# driver1.net
KiCad netlist of a schematic drawn in EAGLE
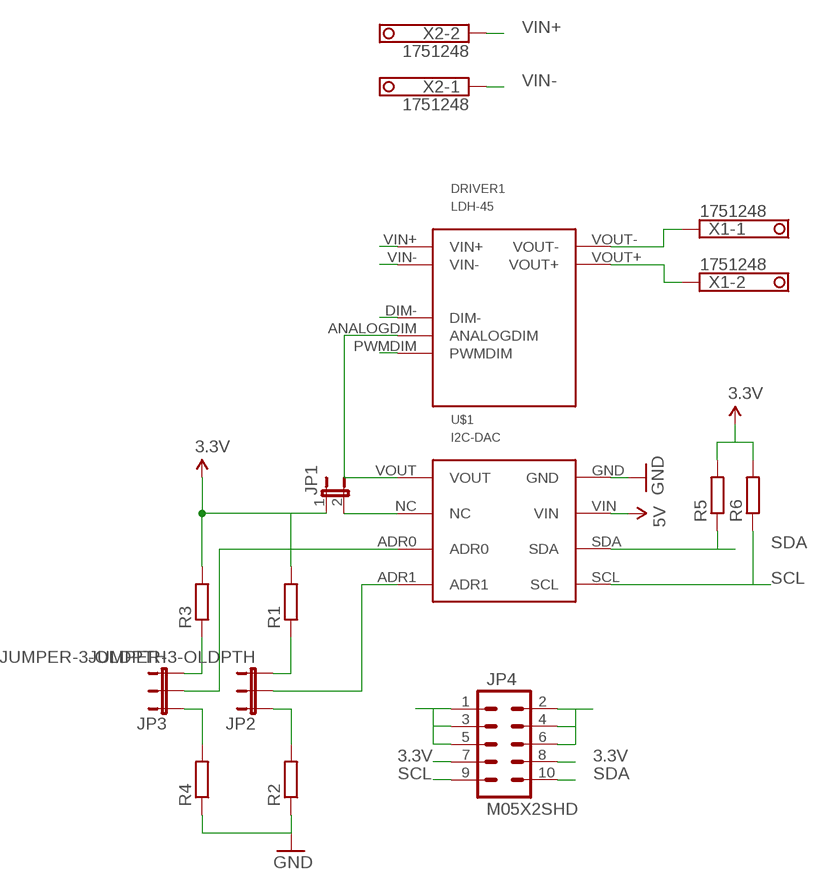
[diagram p0: schematic, sheet 1]

(export (version "E")
  (design (tool "Eeschema 10.0.6"))
  (components
    (comp (ref "DRIVER1")
      (value "LDH-45")
      (footprint "eagle-import:LDH-45")
      (libsource (lib "eagle-import") (part "LDH-45"))
    )
    (comp (ref "JP1")
      (value "JUMPER-2PTH_LOCK")
      (footprint "eagle-import:1X02_LOCK")
      (libsource (lib "eagle-import") (part "JUMPER-2PTH_LOCK"))
    )
    (comp (ref "JP2")
      (value "JUMPER-3-OLDPTH")
      (footprint "eagle-import:1X03")
      (libsource (lib "eagle-import") (part "JUMPER-3-OLDPTH"))
    )
    (comp (ref "JP3")
      (value "JUMPER-3-OLDPTH")
      (footprint "eagle-import:1X03")
      (libsource (lib "eagle-import") (part "JUMPER-3-OLDPTH"))
    )
    (comp (ref "JP4")
      (value "M05X2SHD")
      (footprint "eagle-import:2X5-SHROUDED")
      (libsource (lib "eagle-import") (part "M05X2SHD"))
    )
    (comp (ref "R1")
      (value "R-EU_R0603")
      (footprint "eagle-import:R0603")
      (libsource (lib "eagle-import") (part "R-EU_R0603"))
    )
    (comp (ref "R2")
      (value "R-EU_R0603")
      (footprint "eagle-import:R0603")
      (libsource (lib "eagle-import") (part "R-EU_R0603"))
    )
    (comp (ref "R3")
      (value "R-EU_R0603")
      (footprint "eagle-import:R0603")
      (libsource (lib "eagle-import") (part "R-EU_R0603"))
    )
    (comp (ref "R4")
      (value "R-EU_R0603")
      (footprint "eagle-import:R0603")
      (libsource (lib "eagle-import") (part "R-EU_R0603"))
    )
    (comp (ref "R5")
      (value "R-EU_R0603")
      (footprint "eagle-import:R0603")
      (libsource (lib "eagle-import") (part "R-EU_R0603"))
    )
    (comp (ref "R6")
      (value "R-EU_R0603")
      (footprint "eagle-import:R0603")
      (libsource (lib "eagle-import") (part "R-EU_R0603"))
    )
    (comp (ref "U$1")
      (value "I2C-DAC")
      (footprint "eagle-import:I2C-DAC")
      (libsource (lib "eagle-import") (part "I2C-DAC"))
    )
    (comp (ref "X1")
      (value "1751248")
      (footprint "eagle-import:1751248")
      (libsource (lib "eagle-import") (part "1751248"))
    )
    (comp (ref "X2")
      (value "1751248")
      (footprint "eagle-import:1751248")
      (fields (field (name "OC_FARNELL") "unknown") (field (name "OC_NEWARK") "unknown"))
      (libsource (lib "eagle-import") (part "1751248"))
    )
  )
  (nets
    (net (code "1") (name "/SCL") (class "Default")
      (node (ref "JP4") (pin "9") (pinfunction "9_9") (pintype "passive"))
      (node (ref "R6") (pin "1") (pinfunction "1_1") (pintype "passive"))
      (node (ref "U$1") (pin "SCL") (pinfunction "SCL_SCL") (pintype "bidirectional"))
    )
    (net (code "2") (name "/SDA") (class "Default")
      (node (ref "JP4") (pin "10") (pinfunction "10_10") (pintype "passive"))
      (node (ref "R5") (pin "1") (pinfunction "1_1") (pintype "passive"))
      (node (ref "U$1") (pin "SDA") (pinfunction "SDA_SDA") (pintype "bidirectional"))
    )
    (net (code "3") (name "/VIN+") (class "Default")
      (node (ref "DRIVER1") (pin "VIN+") (pinfunction "VIN+_VIN+") (pintype "bidirectional"))
      (node (ref "X2") (pin "2") (pinfunction "K_2") (pintype "passive"))
    )
    (net (code "4") (name "/VIN-") (class "Default")
      (node (ref "DRIVER1") (pin "VIN-") (pinfunction "VIN-_VIN-") (pintype "bidirectional"))
      (node (ref "X2") (pin "1") (pinfunction "K_1") (pintype "passive"))
    )
    (net (code "5") (name "3.3V") (class "Default")
      (node (ref "JP1") (pin "1") (pinfunction "1_1") (pintype "passive"))
      (node (ref "JP4") (pin "7") (pinfunction "7_7") (pintype "passive"))
      (node (ref "JP4") (pin "8") (pinfunction "8_8") (pintype "passive"))
      (node (ref "R1") (pin "2") (pinfunction "2_2") (pintype "passive"))
      (node (ref "R3") (pin "2") (pinfunction "2_2") (pintype "passive"))
      (node (ref "R5") (pin "2") (pinfunction "2_2") (pintype "passive"))
      (node (ref "R6") (pin "2") (pinfunction "2_2") (pintype "passive"))
    )
    (net (code "6") (name "5V") (class "Default")
      (node (ref "JP4") (pin "2") (pinfunction "2_2") (pintype "passive"))
      (node (ref "JP4") (pin "4") (pinfunction "4_4") (pintype "passive"))
      (node (ref "JP4") (pin "6") (pinfunction "6_6") (pintype "passive"))
      (node (ref "U$1") (pin "VIN") (pinfunction "VIN_VIN") (pintype "bidirectional"))
    )
    (net (code "7") (name "GND") (class "Default")
      (node (ref "JP4") (pin "1") (pinfunction "1_1") (pintype "passive"))
      (node (ref "JP4") (pin "3") (pinfunction "3_3") (pintype "passive"))
      (node (ref "JP4") (pin "5") (pinfunction "5_5") (pintype "passive"))
      (node (ref "R2") (pin "1") (pinfunction "1_1") (pintype "passive"))
      (node (ref "R4") (pin "1") (pinfunction "1_1") (pintype "passive"))
      (node (ref "U$1") (pin "GND") (pinfunction "GND_GND") (pintype "bidirectional"))
    )
    (net (code "8") (name "Net-(DRIVER1-PadANALOGDIM)") (class "Default")
      (node (ref "DRIVER1") (pin "ANALOGDIM") (pinfunction "ANALOGDIM_ANALOGDIM") (pintype "bidirectional"))
      (node (ref "U$1") (pin "VOUT") (pinfunction "VOUT_VOUT") (pintype "bidirectional"))
    )
    (net (code "9") (name "Net-(JP1-Pad2)") (class "Default")
      (node (ref "JP1") (pin "2") (pinfunction "2_2") (pintype "passive"))
      (node (ref "U$1") (pin "NC") (pinfunction "NC_NC") (pintype "bidirectional"))
    )
    (net (code "10") (name "Net-(JP2-Pad1)") (class "Default")
      (node (ref "JP2") (pin "1") (pinfunction "1_1") (pintype "passive"))
      (node (ref "R2") (pin "2") (pinfunction "2_2") (pintype "passive"))
    )
    (net (code "11") (name "Net-(JP2-Pad2)") (class "Default")
      (node (ref "JP2") (pin "2") (pinfunction "2_2") (pintype "passive"))
      (node (ref "U$1") (pin "ADR1") (pinfunction "ADR1_ADR1") (pintype "bidirectional"))
    )
    (net (code "12") (name "Net-(JP2-Pad3)") (class "Default")
      (node (ref "JP2") (pin "3") (pinfunction "3_3") (pintype "passive"))
      (node (ref "R1") (pin "1") (pinfunction "1_1") (pintype "passive"))
    )
    (net (code "13") (name "Net-(JP3-Pad1)") (class "Default")
      (node (ref "JP3") (pin "1") (pinfunction "1_1") (pintype "passive"))
      (node (ref "R4") (pin "2") (pinfunction "2_2") (pintype "passive"))
    )
    (net (code "14") (name "Net-(JP3-Pad2)") (class "Default")
      (node (ref "JP3") (pin "2") (pinfunction "2_2") (pintype "passive"))
      (node (ref "U$1") (pin "ADR0") (pinfunction "ADR0_ADR0") (pintype "bidirectional"))
    )
    (net (code "15") (name "Net-(JP3-Pad3)") (class "Default")
      (node (ref "JP3") (pin "3") (pinfunction "3_3") (pintype "passive"))
      (node (ref "R3") (pin "1") (pinfunction "1_1") (pintype "passive"))
    )
    (net (code "16") (name "Net-(X1A-K)") (class "Default")
      (node (ref "DRIVER1") (pin "VOUT-") (pinfunction "VOUT-_VOUT-") (pintype "bidirectional"))
      (node (ref "X1") (pin "1") (pinfunction "K_1") (pintype "passive"))
    )
    (net (code "17") (name "Net-(X1B-K)") (class "Default")
      (node (ref "DRIVER1") (pin "VOUT+") (pinfunction "VOUT+_VOUT+") (pintype "bidirectional"))
      (node (ref "X1") (pin "2") (pinfunction "K_2") (pintype "passive"))
    )
    (net (code "18") (name "unconnected-(DRIVER1-PadDIM-)") (class "Default")
      (node (ref "DRIVER1") (pin "DIM-") (pinfunction "DIM-_DIM-") (pintype "bidirectional"))
    )
    (net (code "19") (name "unconnected-(DRIVER1-PadPWMDIM)") (class "Default")
      (node (ref "DRIVER1") (pin "PWMDIM") (pinfunction "PWMDIM_PWMDIM") (pintype "bidirectional"))
    )
  )
)
